# EPS_MPPT_X_EMI-Filter_Out.net
KiCad netlist of a schematic drawn in Altium Designer
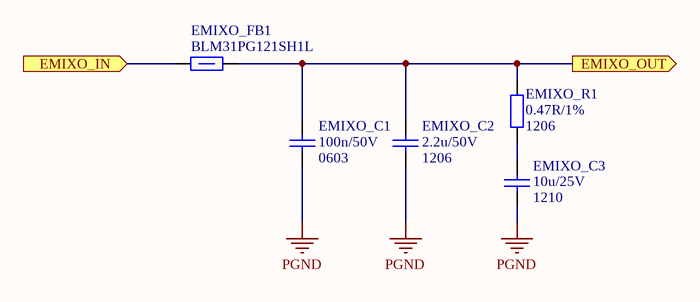
[diagram p0: EPS_MPPT_X_EMI-Filter_Out.SchDoc]

(export (version "E")
  (design (tool "Eeschema 10.0.6"))
  (components
    (comp (ref "EMIXO_C1")
      (value "100n/50V")
      (footprint "SMD_Capacitor_0603")
      (description "Ceramic Cap Kemet COTS 100n/50V X7R 0603")
      (fields
        (field (name "MANUFACTURER") "Kemet")
        (field (name "MANUFACTURERPARTNUMBER") "C0603T104K5RALTU")
        (field (name "PACKAGE") "0603")
      )
      (libsource (lib "capacitors") (part "Cer_C0603T104K5RALTU"))
    )
    (comp (ref "EMIXO_C2")
      (value "2.2u/50V")
      (footprint "SMD_Capacitor_1206")
      (description "Ceramic Cap Murata Automotive 2.2u/50V X7R 1206")
      (fields
        (field (name "MANUFACTURER") "Murata")
        (field (name "MANUFACTURERPARTNUMBER") "GCJ31CR71H225KA12L")
        (field (name "PACKAGE") "1206")
      )
      (libsource (lib "capacitors") (part "Cer_GCJ31CR71H225KA12L"))
    )
    (comp (ref "EMIXO_C3")
      (value "10u/25V")
      (footprint "SMD_Capacitor_1210")
      (description "Ceramic Cap Murata Automotive 10u/25V X7R 1210")
      (fields
        (field (name "MANUFACTURER") "Murata")
        (field (name "MANUFACTURERPARTNUMBER") "GCJ32ER71E106KA12L")
        (field (name "PACKAGE") "1210")
      )
      (libsource (lib "capacitors") (part "Cer_GCJ32ER71E106KA12L"))
    )
    (comp (ref "EMIXO_FB1")
      (value "120R/100MHz")
      (footprint "SMD_FerriteBead_1206")
      (description "Ferrite bead, 1206, 0.02HM, 3.5A.")
      (fields (field (name "MANUFACTURER") "Murata") (field (name "MANUFACTURERPARTNUMBER") "BLM31PG121SH1L"))
      (libsource (lib "inductors") (part "BLM31PG121SH1L"))
    )
    (comp (ref "EMIXO_R1")
      (value "0.47R/1%")
      (footprint "SMD_Resistor_1206")
      (description "Panasonic Resistor 0.47R 1% 1206 330mW")
      (fields
        (field (name "MANUFACTURERPARTNUMBER") "ERJ-8BQFR47V")
        (field (name "MANUFACTURER") "Panasonic")
        (field (name "PACKAGE") "1206")
      )
      (libsource (lib "resistors") (part "ERJ-8BQFR47V"))
    )
  )
  (nets
    (net (code "1") (name "/EMIXO_IN") (class "Default")
      (node (ref "EMIXO_FB1") (pin "2") (pinfunction "2_2") (pintype "passive"))
    )
    (net (code "2") (name "/EMIXO_OUT") (class "Default")
      (node (ref "EMIXO_C1") (pin "1") (pinfunction "1_1") (pintype "passive"))
      (node (ref "EMIXO_C2") (pin "1") (pinfunction "1_1") (pintype "passive"))
      (node (ref "EMIXO_FB1") (pin "1") (pinfunction "1_1") (pintype "passive"))
      (node (ref "EMIXO_R1") (pin "2") (pinfunction "2_2") (pintype "passive"))
    )
    (net (code "3") (name "Net-(EMIXO_C3-Pad1)") (class "Default")
      (node (ref "EMIXO_C3") (pin "1") (pinfunction "1_1") (pintype "passive"))
      (node (ref "EMIXO_R1") (pin "1") (pinfunction "1_1") (pintype "passive"))
    )
    (net (code "4") (name "PGND") (class "Default")
      (node (ref "EMIXO_C1") (pin "2") (pinfunction "2_2") (pintype "passive"))
      (node (ref "EMIXO_C2") (pin "2") (pinfunction "2_2") (pintype "passive"))
      (node (ref "EMIXO_C3") (pin "2") (pinfunction "2_2") (pintype "passive"))
    )
  )
)
